# main.net
KiCad netlist of a schematic drawn in Altium Designer
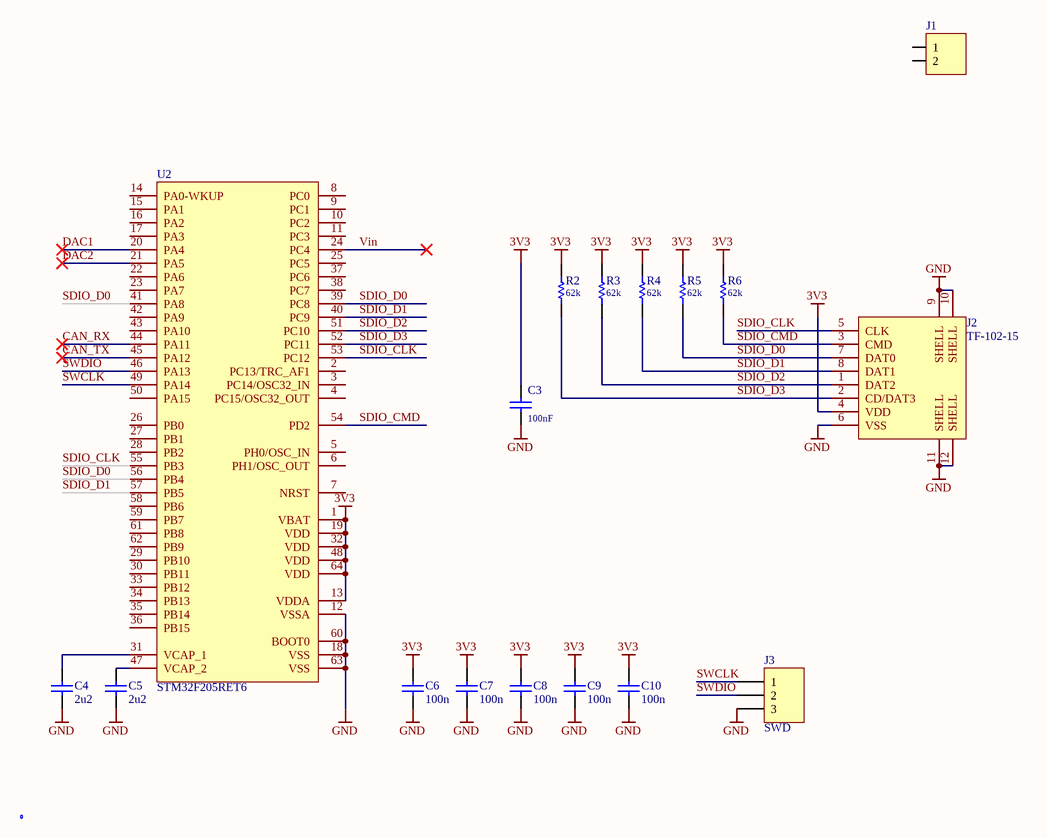
[diagram p0: main.SchDoc]

(export (version "E")
  (design (tool "Eeschema 10.0.6"))
  (components
    (comp (ref "C3")
      (value "100nF")
      (footprint "C0402")
      (fields (field (name "LCSC PART NUMBER") "C131394"))
      (libsource (lib "Miscellaneous Devices") (part "CAP"))
    )
    (comp (ref "C4") (value "2u2") (footprint "C0603") (libsource (lib "Miscellaneous Devices") (part "Cap")))
    (comp (ref "C5") (value "2u2") (footprint "C0603") (libsource (lib "Miscellaneous Devices") (part "Cap")))
    (comp (ref "C6")
      (value "100n")
      (footprint "C0402")
      (libsource (lib "Miscellaneous Devices") (part "Cap"))
    )
    (comp (ref "C7")
      (value "100n")
      (footprint "C0402")
      (libsource (lib "Miscellaneous Devices") (part "Cap"))
    )
    (comp (ref "C8")
      (value "100n")
      (footprint "C0402")
      (libsource (lib "Miscellaneous Devices") (part "Cap"))
    )
    (comp (ref "C9")
      (value "100n")
      (footprint "C0402")
      (libsource (lib "Miscellaneous Devices") (part "Cap"))
    )
    (comp (ref "C10")
      (value "100n")
      (footprint "C0402")
      (libsource (lib "Miscellaneous Devices") (part "Cap"))
    )
    (comp (ref "J1") (value "~") (footprint "HDR-1X2_2.54") (libsource (lib "Schlib1") (part "Header 2")))
    (comp (ref "J2")
      (value "TF-102-15")
      (footprint "TF-SMD_TF-102-15")
      (libsource (lib "Schlib2") (part "TF-102-15"))
    )
    (comp (ref "J3")
      (value "SWD")
      (footprint "HDR-1x3-P1.25")
      (libsource (lib "Miscellaneous Devices") (part "Header 3"))
    )
    (comp (ref "LOGO1") (value "LOGO") (footprint "LOGO") (libsource (lib "Schlib1") (part "LOGO")))
    (comp (ref "R2") (value "62k") (footprint "R0402") (libsource (lib "RR_Passive") (part "RES")))
    (comp (ref "R3") (value "62k") (footprint "R0402") (libsource (lib "RR_Passive") (part "RES")))
    (comp (ref "R4") (value "62k") (footprint "R0402") (libsource (lib "RR_Passive") (part "RES")))
    (comp (ref "R5") (value "62k") (footprint "R0402") (libsource (lib "RR_Passive") (part "RES")))
    (comp (ref "R6") (value "62k") (footprint "R0402") (libsource (lib "RR_Passive") (part "RES")))
    (comp (ref "U2")
      (value "STM32F205RET6")
      (footprint "LQFP-64")
      (fields (field (name "MANUFACTURER") "ST(意法半导体)"))
      (libsource (lib "Schlib1") (part "STM32F205RET6"))
    )
  )
  (nets
    (net (code "1") (name "/CAN_RX") (class "Default")
      (node (ref "U2") (pin "44") (pinfunction "PA11_44") (pintype "passive+no_connect"))
    )
    (net (code "2") (name "/CAN_TX") (class "Default")
      (node (ref "U2") (pin "45") (pinfunction "PA12_45") (pintype "passive+no_connect"))
    )
    (net (code "3") (name "/DAC1") (class "Default")
      (node (ref "U2") (pin "20") (pinfunction "PA4_20") (pintype "passive+no_connect"))
    )
    (net (code "4") (name "/DAC2") (class "Default")
      (node (ref "U2") (pin "21") (pinfunction "PA5_21") (pintype "passive+no_connect"))
    )
    (net (code "5") (name "/SDIO_CLK") (class "Default")
      (node (ref "J2") (pin "5") (pinfunction "CLK_5") (pintype "passive"))
      (node (ref "U2") (pin "53") (pinfunction "PC12_53") (pintype "passive"))
      (node (ref "U2") (pin "55") (pinfunction "PB3_55") (pintype "passive"))
    )
    (net (code "6") (name "/SDIO_CMD") (class "Default")
      (node (ref "J2") (pin "3") (pinfunction "CMD_3") (pintype "passive"))
      (node (ref "R6") (pin "2") (pinfunction "2_2") (pintype "passive"))
      (node (ref "U2") (pin "54") (pinfunction "PD2_54") (pintype "passive"))
    )
    (net (code "7") (name "/SDIO_D0") (class "Default")
      (node (ref "J2") (pin "7") (pinfunction "DAT0_7") (pintype "passive"))
      (node (ref "R5") (pin "2") (pinfunction "2_2") (pintype "passive"))
      (node (ref "U2") (pin "39") (pinfunction "PC8_39") (pintype "passive"))
      (node (ref "U2") (pin "41") (pinfunction "PA8_41") (pintype "passive"))
      (node (ref "U2") (pin "56") (pinfunction "PB4_56") (pintype "passive"))
    )
    (net (code "8") (name "/SDIO_D1") (class "Default")
      (node (ref "J2") (pin "8") (pinfunction "DAT1_8") (pintype "passive"))
      (node (ref "R4") (pin "2") (pinfunction "2_2") (pintype "passive"))
      (node (ref "U2") (pin "40") (pinfunction "PC9_40") (pintype "passive"))
      (node (ref "U2") (pin "57") (pinfunction "PB5_57") (pintype "passive"))
    )
    (net (code "9") (name "/SDIO_D2") (class "Default")
      (node (ref "J2") (pin "1") (pinfunction "DAT2_1") (pintype "passive"))
      (node (ref "R3") (pin "2") (pinfunction "2_2") (pintype "passive"))
      (node (ref "U2") (pin "51") (pinfunction "PC10_51") (pintype "passive"))
    )
    (net (code "10") (name "/SDIO_D3") (class "Default")
      (node (ref "J2") (pin "2") (pinfunction "CD/DAT3_2") (pintype "passive"))
      (node (ref "R2") (pin "2") (pinfunction "2_2") (pintype "passive"))
      (node (ref "U2") (pin "52") (pinfunction "PC11_52") (pintype "passive"))
    )
    (net (code "11") (name "/SWCLK") (class "Default")
      (node (ref "J3") (pin "1") (pinfunction "1_1") (pintype "passive"))
      (node (ref "U2") (pin "49") (pinfunction "PA14_49") (pintype "passive"))
    )
    (net (code "12") (name "/SWDIO") (class "Default")
      (node (ref "J3") (pin "2") (pinfunction "2_2") (pintype "passive"))
      (node (ref "U2") (pin "46") (pinfunction "PA13_46") (pintype "passive"))
    )
    (net (code "13") (name "/Vin") (class "Default")
      (node (ref "U2") (pin "24") (pinfunction "PC4_24") (pintype "passive+no_connect"))
    )
    (net (code "14") (name "3V3") (class "Default")
      (node (ref "C10") (pin "2") (pinfunction "2_2") (pintype "passive"))
      (node (ref "C3") (pin "2") (pinfunction "2_2") (pintype "passive"))
      (node (ref "C6") (pin "2") (pinfunction "2_2") (pintype "passive"))
      (node (ref "C7") (pin "2") (pinfunction "2_2") (pintype "passive"))
      (node (ref "C8") (pin "2") (pinfunction "2_2") (pintype "passive"))
      (node (ref "C9") (pin "2") (pinfunction "2_2") (pintype "passive"))
      (node (ref "J2") (pin "4") (pinfunction "VDD_4") (pintype "passive"))
      (node (ref "R2") (pin "1") (pinfunction "1_1") (pintype "passive"))
      (node (ref "R3") (pin "1") (pinfunction "1_1") (pintype "passive"))
      (node (ref "R4") (pin "1") (pinfunction "1_1") (pintype "passive"))
      (node (ref "R5") (pin "1") (pinfunction "1_1") (pintype "passive"))
      (node (ref "R6") (pin "1") (pinfunction "1_1") (pintype "passive"))
      (node (ref "U2") (pin "1") (pinfunction "VBAT_1") (pintype "passive"))
      (node (ref "U2") (pin "13") (pinfunction "VDDA_13") (pintype "passive"))
      (node (ref "U2") (pin "19") (pinfunction "VDD_19") (pintype "passive"))
      (node (ref "U2") (pin "32") (pinfunction "VDD_32") (pintype "passive"))
      (node (ref "U2") (pin "48") (pinfunction "VDD_48") (pintype "passive"))
      (node (ref "U2") (pin "64") (pinfunction "VDD_64") (pintype "passive"))
    )
    (net (code "15") (name "GND") (class "Default")
      (node (ref "C10") (pin "1") (pinfunction "1_1") (pintype "passive"))
      (node (ref "C3") (pin "1") (pinfunction "1_1") (pintype "passive"))
      (node (ref "C4") (pin "1") (pinfunction "1_1") (pintype "passive"))
      (node (ref "C5") (pin "1") (pinfunction "1_1") (pintype "passive"))
      (node (ref "C6") (pin "1") (pinfunction "1_1") (pintype "passive"))
      (node (ref "C7") (pin "1") (pinfunction "1_1") (pintype "passive"))
      (node (ref "C8") (pin "1") (pinfunction "1_1") (pintype "passive"))
      (node (ref "C9") (pin "1") (pinfunction "1_1") (pintype "passive"))
      (node (ref "J2") (pin "10") (pinfunction "SHELL_10") (pintype "passive"))
      (node (ref "J2") (pin "11") (pinfunction "SHELL_11") (pintype "passive"))
      (node (ref "J2") (pin "12") (pinfunction "SHELL_12") (pintype "passive"))
      (node (ref "J2") (pin "6") (pinfunction "VSS_6") (pintype "passive"))
      (node (ref "J2") (pin "9") (pinfunction "SHELL_9") (pintype "passive"))
      (node (ref "J3") (pin "3") (pinfunction "3_3") (pintype "passive"))
      (node (ref "U2") (pin "12") (pinfunction "VSSA_12") (pintype "passive"))
      (node (ref "U2") (pin "18") (pinfunction "VSS_18") (pintype "passive"))
      (node (ref "U2") (pin "60") (pinfunction "BOOT0_60") (pintype "passive"))
      (node (ref "U2") (pin "63") (pinfunction "VSS_63") (pintype "passive"))
    )
    (net (code "16") (name "Net-(U2-VCAP_1)") (class "Default")
      (node (ref "C4") (pin "2") (pinfunction "2_2") (pintype "passive"))
      (node (ref "U2") (pin "31") (pinfunction "VCAP_1_31") (pintype "passive"))
    )
    (net (code "17") (name "Net-(U2-VCAP_2)") (class "Default")
      (node (ref "C5") (pin "2") (pinfunction "2_2") (pintype "passive"))
      (node (ref "U2") (pin "47") (pinfunction "VCAP_2_47") (pintype "passive"))
    )
    (net (code "18") (name "unconnected-(J1-Pad1)") (class "Default")
      (node (ref "J1") (pin "1") (pinfunction "1_1") (pintype "passive"))
    )
    (net (code "19") (name "unconnected-(J1-Pad2)") (class "Default")
      (node (ref "J1") (pin "2") (pinfunction "2_2") (pintype "passive"))
    )
    (net (code "20") (name "unconnected-(U2-NRST-Pad7)") (class "Default")
      (node (ref "U2") (pin "7") (pinfunction "NRST_7") (pintype "passive"))
    )
    (net (code "21") (name "unconnected-(U2-PA0-WKUP-Pad14)") (class "Default")
      (node (ref "U2") (pin "14") (pinfunction "PA0-WKUP_14") (pintype "passive"))
    )
    (net (code "22") (name "unconnected-(U2-PA1-Pad15)") (class "Default")
      (node (ref "U2") (pin "15") (pinfunction "PA1_15") (pintype "passive"))
    )
    (net (code "23") (name "unconnected-(U2-PA2-Pad16)") (class "Default")
      (node (ref "U2") (pin "16") (pinfunction "PA2_16") (pintype "passive"))
    )
    (net (code "24") (name "unconnected-(U2-PA3-Pad17)") (class "Default")
      (node (ref "U2") (pin "17") (pinfunction "PA3_17") (pintype "passive"))
    )
    (net (code "25") (name "unconnected-(U2-PA6-Pad22)") (class "Default")
      (node (ref "U2") (pin "22") (pinfunction "PA6_22") (pintype "passive"))
    )
    (net (code "26") (name "unconnected-(U2-PA7-Pad23)") (class "Default")
      (node (ref "U2") (pin "23") (pinfunction "PA7_23") (pintype "passive"))
    )
    (net (code "27") (name "unconnected-(U2-PA9-Pad42)") (class "Default")
      (node (ref "U2") (pin "42") (pinfunction "PA9_42") (pintype "passive"))
    )
    (net (code "28") (name "unconnected-(U2-PA10-Pad43)") (class "Default")
      (node (ref "U2") (pin "43") (pinfunction "PA10_43") (pintype "passive"))
    )
    (net (code "29") (name "unconnected-(U2-PA15-Pad50)") (class "Default")
      (node (ref "U2") (pin "50") (pinfunction "PA15_50") (pintype "passive"))
    )
    (net (code "30") (name "unconnected-(U2-PB0-Pad26)") (class "Default")
      (node (ref "U2") (pin "26") (pinfunction "PB0_26") (pintype "passive"))
    )
    (net (code "31") (name "unconnected-(U2-PB1-Pad27)") (class "Default")
      (node (ref "U2") (pin "27") (pinfunction "PB1_27") (pintype "passive"))
    )
    (net (code "32") (name "unconnected-(U2-PB2-Pad28)") (class "Default")
      (node (ref "U2") (pin "28") (pinfunction "PB2_28") (pintype "passive"))
    )
    (net (code "33") (name "unconnected-(U2-PB6-Pad58)") (class "Default")
      (node (ref "U2") (pin "58") (pinfunction "PB6_58") (pintype "passive"))
    )
    (net (code "34") (name "unconnected-(U2-PB7-Pad59)") (class "Default")
      (node (ref "U2") (pin "59") (pinfunction "PB7_59") (pintype "passive"))
    )
    (net (code "35") (name "unconnected-(U2-PB8-Pad61)") (class "Default")
      (node (ref "U2") (pin "61") (pinfunction "PB8_61") (pintype "passive"))
    )
    (net (code "36") (name "unconnected-(U2-PB9-Pad62)") (class "Default")
      (node (ref "U2") (pin "62") (pinfunction "PB9_62") (pintype "passive"))
    )
    (net (code "37") (name "unconnected-(U2-PB10-Pad29)") (class "Default")
      (node (ref "U2") (pin "29") (pinfunction "PB10_29") (pintype "passive"))
    )
    (net (code "38") (name "unconnected-(U2-PB11-Pad30)") (class "Default")
      (node (ref "U2") (pin "30") (pinfunction "PB11_30") (pintype "passive"))
    )
    (net (code "39") (name "unconnected-(U2-PB12-Pad33)") (class "Default")
      (node (ref "U2") (pin "33") (pinfunction "PB12_33") (pintype "passive"))
    )
    (net (code "40") (name "unconnected-(U2-PB13-Pad34)") (class "Default")
      (node (ref "U2") (pin "34") (pinfunction "PB13_34") (pintype "passive"))
    )
    (net (code "41") (name "unconnected-(U2-PB14-Pad35)") (class "Default")
      (node (ref "U2") (pin "35") (pinfunction "PB14_35") (pintype "passive"))
    )
    (net (code "42") (name "unconnected-(U2-PB15-Pad36)") (class "Default")
      (node (ref "U2") (pin "36") (pinfunction "PB15_36") (pintype "passive"))
    )
    (net (code "43") (name "unconnected-(U2-PC0-Pad8)") (class "Default")
      (node (ref "U2") (pin "8") (pinfunction "PC0_8") (pintype "passive"))
    )
    (net (code "44") (name "unconnected-(U2-PC1-Pad9)") (class "Default")
      (node (ref "U2") (pin "9") (pinfunction "PC1_9") (pintype "passive"))
    )
    (net (code "45") (name "unconnected-(U2-PC2-Pad10)") (class "Default")
      (node (ref "U2") (pin "10") (pinfunction "PC2_10") (pintype "passive"))
    )
    (net (code "46") (name "unconnected-(U2-PC3-Pad11)") (class "Default")
      (node (ref "U2") (pin "11") (pinfunction "PC3_11") (pintype "passive"))
    )
    (net (code "47") (name "unconnected-(U2-PC5-Pad25)") (class "Default")
      (node (ref "U2") (pin "25") (pinfunction "PC5_25") (pintype "passive"))
    )
    (net (code "48") (name "unconnected-(U2-PC6-Pad37)") (class "Default")
      (node (ref "U2") (pin "37") (pinfunction "PC6_37") (pintype "passive"))
    )
    (net (code "49") (name "unconnected-(U2-PC7-Pad38)") (class "Default")
      (node (ref "U2") (pin "38") (pinfunction "PC7_38") (pintype "passive"))
    )
    (net (code "50") (name "unconnected-(U2-PC13{slash}TRC_AF1-Pad2)") (class "Default")
      (node (ref "U2") (pin "2") (pinfunction "PC13/TRC_AF1_2") (pintype "passive"))
    )
    (net (code "51") (name "unconnected-(U2-PC14{slash}OSC32_IN-Pad3)") (class "Default")
      (node (ref "U2") (pin "3") (pinfunction "PC14/OSC32_IN_3") (pintype "passive"))
    )
    (net (code "52") (name "unconnected-(U2-PC15{slash}OSC32_OUT-Pad4)") (class "Default")
      (node (ref "U2") (pin "4") (pinfunction "PC15/OSC32_OUT_4") (pintype "passive"))
    )
    (net (code "53") (name "unconnected-(U2-PH0{slash}OSC_IN-Pad5)") (class "Default")
      (node (ref "U2") (pin "5") (pinfunction "PH0/OSC_IN_5") (pintype "passive"))
    )
    (net (code "54") (name "unconnected-(U2-PH1{slash}OSC_OUT-Pad6)") (class "Default")
      (node (ref "U2") (pin "6") (pinfunction "PH1/OSC_OUT_6") (pintype "passive"))
    )
  )
)
